# MIDI-daughter-board.net
KiCad netlist of a schematic drawn in EAGLE
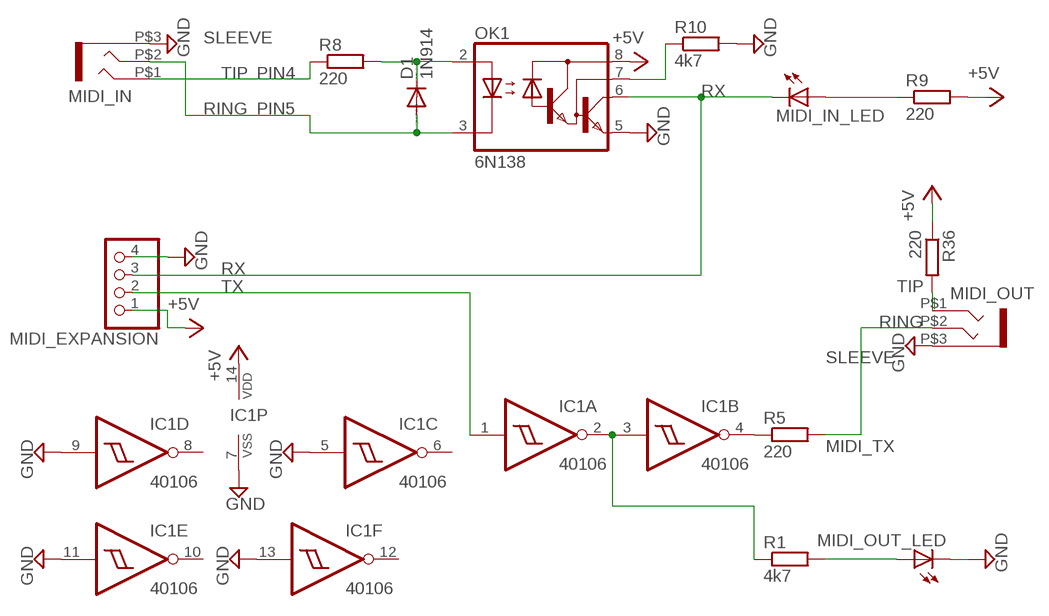
[diagram p0: schematic, sheet 1]

(export (version "E")
  (design (tool "Eeschema 10.0.6"))
  (components
    (comp (ref "D1")
      (value "1N914")
      (footprint "eagle-import:D-6.35")
      (libsource (lib "eagle-import") (part "1N914"))
    )
    (comp (ref "IC1")
      (value "40106")
      (footprint "eagle-import:DIL14")
      (libsource (lib "eagle-import") (part "40106N"))
    )
    (comp (ref "MIDI_EXPANSION")
      (value "PINHD-1X4")
      (footprint "eagle-import:1X04")
      (libsource (lib "eagle-import") (part "PINHD-1X4"))
    )
    (comp (ref "MIDI_IN")
      (value "WQP-PJ301M-STEREO")
      (footprint "eagle-import:WQP-PJ301M-STEREO")
      (libsource (lib "eagle-import") (part "WQP-PJ301M-STEREO"))
    )
    (comp (ref "MIDI_IN_LED")
      (value "LED3MM-NB")
      (footprint "eagle-import:LED3MM")
      (libsource (lib "eagle-import") (part "LED3MM-NB"))
    )
    (comp (ref "MIDI_OUT")
      (value "WQP-PJ301M-STEREO")
      (footprint "eagle-import:WQP-PJ301M-STEREO")
      (libsource (lib "eagle-import") (part "WQP-PJ301M-STEREO"))
    )
    (comp (ref "MIDI_OUT_LED")
      (value "LED3MM-NB")
      (footprint "eagle-import:LED3MM")
      (libsource (lib "eagle-import") (part "LED3MM-NB"))
    )
    (comp (ref "OK1")
      (value "6N138")
      (footprint "eagle-import:DIL08")
      (fields (field (name "MF") "VISHAY/TELEFUNKEN"))
      (libsource (lib "eagle-import") (part "6N138"))
    )
    (comp (ref "R1")
      (value "4k7")
      (footprint "eagle-import:0204_7")
      (libsource (lib "eagle-import") (part "BOX-RESISTOR"))
    )
    (comp (ref "R5")
      (value "220")
      (footprint "eagle-import:0204_7")
      (libsource (lib "eagle-import") (part "BOX-RESISTOR"))
    )
    (comp (ref "R8")
      (value "220")
      (footprint "eagle-import:0204_7")
      (libsource (lib "eagle-import") (part "BOX-RESISTOR"))
    )
    (comp (ref "R9")
      (value "220")
      (footprint "eagle-import:0204_7")
      (libsource (lib "eagle-import") (part "BOX-RESISTOR"))
    )
    (comp (ref "R10")
      (value "4k7")
      (footprint "eagle-import:0204_7")
      (libsource (lib "eagle-import") (part "BOX-RESISTOR"))
    )
    (comp (ref "R36")
      (value "220")
      (footprint "eagle-import:0204_7")
      (libsource (lib "eagle-import") (part "BOX-RESISTOR"))
    )
  )
  (nets
    (net (code "1") (name "+5V") (class "Default")
      (node (ref "IC1") (pin "14") (pinfunction "VDD_14") (pintype "power_in"))
      (node (ref "MIDI_EXPANSION") (pin "1") (pinfunction "1_1") (pintype "passive"))
      (node (ref "OK1") (pin "8") (pinfunction "VCC_8") (pintype "passive"))
      (node (ref "R36") (pin "1") (pinfunction "1_1") (pintype "passive"))
      (node (ref "R9") (pin "2") (pinfunction "2_2") (pintype "passive"))
    )
    (net (code "2") (name "/MIDI_TX") (class "Default")
      (node (ref "MIDI_OUT") (pin "P$2") (pinfunction "3_P$2") (pintype "passive"))
      (node (ref "R5") (pin "2") (pinfunction "2_2") (pintype "passive"))
    )
    (net (code "3") (name "/PIN4") (class "Default")
      (node (ref "MIDI_IN") (pin "P$1") (pinfunction "2_P$1") (pintype "passive"))
      (node (ref "R8") (pin "1") (pinfunction "1_1") (pintype "passive"))
    )
    (net (code "4") (name "/PIN5") (class "Default")
      (node (ref "D1") (pin "A") (pinfunction "A_A") (pintype "passive"))
      (node (ref "MIDI_IN") (pin "P$2") (pinfunction "3_P$2") (pintype "passive"))
      (node (ref "OK1") (pin "3") (pinfunction "C_3") (pintype "passive"))
    )
    (net (code "5") (name "/RX") (class "Default")
      (node (ref "MIDI_EXPANSION") (pin "3") (pinfunction "3_3") (pintype "passive"))
      (node (ref "MIDI_IN_LED") (pin "K") (pinfunction "C_K") (pintype "passive"))
      (node (ref "OK1") (pin "6") (pinfunction "VO_6") (pintype "passive"))
    )
    (net (code "6") (name "/TX") (class "Default")
      (node (ref "IC1") (pin "1") (pinfunction "I_1") (pintype "input"))
      (node (ref "MIDI_EXPANSION") (pin "2") (pinfunction "2_2") (pintype "passive"))
    )
    (net (code "7") (name "GND") (class "Default")
      (node (ref "IC1") (pin "11") (pinfunction "I_11") (pintype "input"))
      (node (ref "IC1") (pin "13") (pinfunction "I_13") (pintype "input"))
      (node (ref "IC1") (pin "5") (pinfunction "I_5") (pintype "input"))
      (node (ref "IC1") (pin "7") (pinfunction "VSS_7") (pintype "power_in"))
      (node (ref "IC1") (pin "9") (pinfunction "I_9") (pintype "input"))
      (node (ref "MIDI_EXPANSION") (pin "4") (pinfunction "4_4") (pintype "passive"))
      (node (ref "MIDI_IN") (pin "P$3") (pinfunction "1_P$3") (pintype "passive"))
      (node (ref "MIDI_OUT") (pin "P$3") (pinfunction "1_P$3") (pintype "passive"))
      (node (ref "MIDI_OUT_LED") (pin "K") (pinfunction "C_K") (pintype "passive"))
      (node (ref "OK1") (pin "5") (pinfunction "GND_5") (pintype "passive"))
      (node (ref "R10") (pin "2") (pinfunction "2_2") (pintype "passive"))
    )
    (net (code "8") (name "Net-(IC1A-O)") (class "Default")
      (node (ref "IC1") (pin "2") (pinfunction "O_2") (pintype "output"))
      (node (ref "IC1") (pin "3") (pinfunction "I_3") (pintype "input"))
      (node (ref "R1") (pin "1") (pinfunction "1_1") (pintype "passive"))
    )
    (net (code "9") (name "Net-(IC1B-O)") (class "Default")
      (node (ref "IC1") (pin "4") (pinfunction "O_4") (pintype "output"))
      (node (ref "R5") (pin "1") (pinfunction "1_1") (pintype "passive"))
    )
    (net (code "10") (name "Net-(MIDI_IN_LED-PadA)") (class "Default")
      (node (ref "MIDI_IN_LED") (pin "A") (pinfunction "A_A") (pintype "passive"))
      (node (ref "R9") (pin "1") (pinfunction "1_1") (pintype "passive"))
    )
    (net (code "11") (name "Net-(MIDI_OUT-2)") (class "Default")
      (node (ref "MIDI_OUT") (pin "P$1") (pinfunction "2_P$1") (pintype "passive"))
      (node (ref "R36") (pin "2") (pinfunction "2_2") (pintype "passive"))
    )
    (net (code "12") (name "Net-(MIDI_OUT_LED-PadA)") (class "Default")
      (node (ref "MIDI_OUT_LED") (pin "A") (pinfunction "A_A") (pintype "passive"))
      (node (ref "R1") (pin "2") (pinfunction "2_2") (pintype "passive"))
    )
    (net (code "13") (name "Net-(OK1-A)") (class "Default")
      (node (ref "D1") (pin "C") (pinfunction "C_C") (pintype "passive"))
      (node (ref "OK1") (pin "2") (pinfunction "A_2") (pintype "passive"))
      (node (ref "R8") (pin "2") (pinfunction "2_2") (pintype "passive"))
    )
    (net (code "14") (name "Net-(OK1-VB)") (class "Default")
      (node (ref "OK1") (pin "7") (pinfunction "VB_7") (pintype "passive"))
      (node (ref "R10") (pin "1") (pinfunction "1_1") (pintype "passive"))
    )
    (net (code "15") (name "unconnected-(IC1C-O-Pad6)") (class "Default")
      (node (ref "IC1") (pin "6") (pinfunction "O_6") (pintype "output"))
    )
    (net (code "16") (name "unconnected-(IC1D-O-Pad8)") (class "Default")
      (node (ref "IC1") (pin "8") (pinfunction "O_8") (pintype "output"))
    )
    (net (code "17") (name "unconnected-(IC1E-O-Pad10)") (class "Default")
      (node (ref "IC1") (pin "10") (pinfunction "O_10") (pintype "output"))
    )
    (net (code "18") (name "unconnected-(IC1F-O-Pad12)") (class "Default")
      (node (ref "IC1") (pin "12") (pinfunction "O_12") (pintype "output"))
    )
  )
)
